# CC_amplifier.net
KiCad netlist of a schematic drawn in Altium Designer
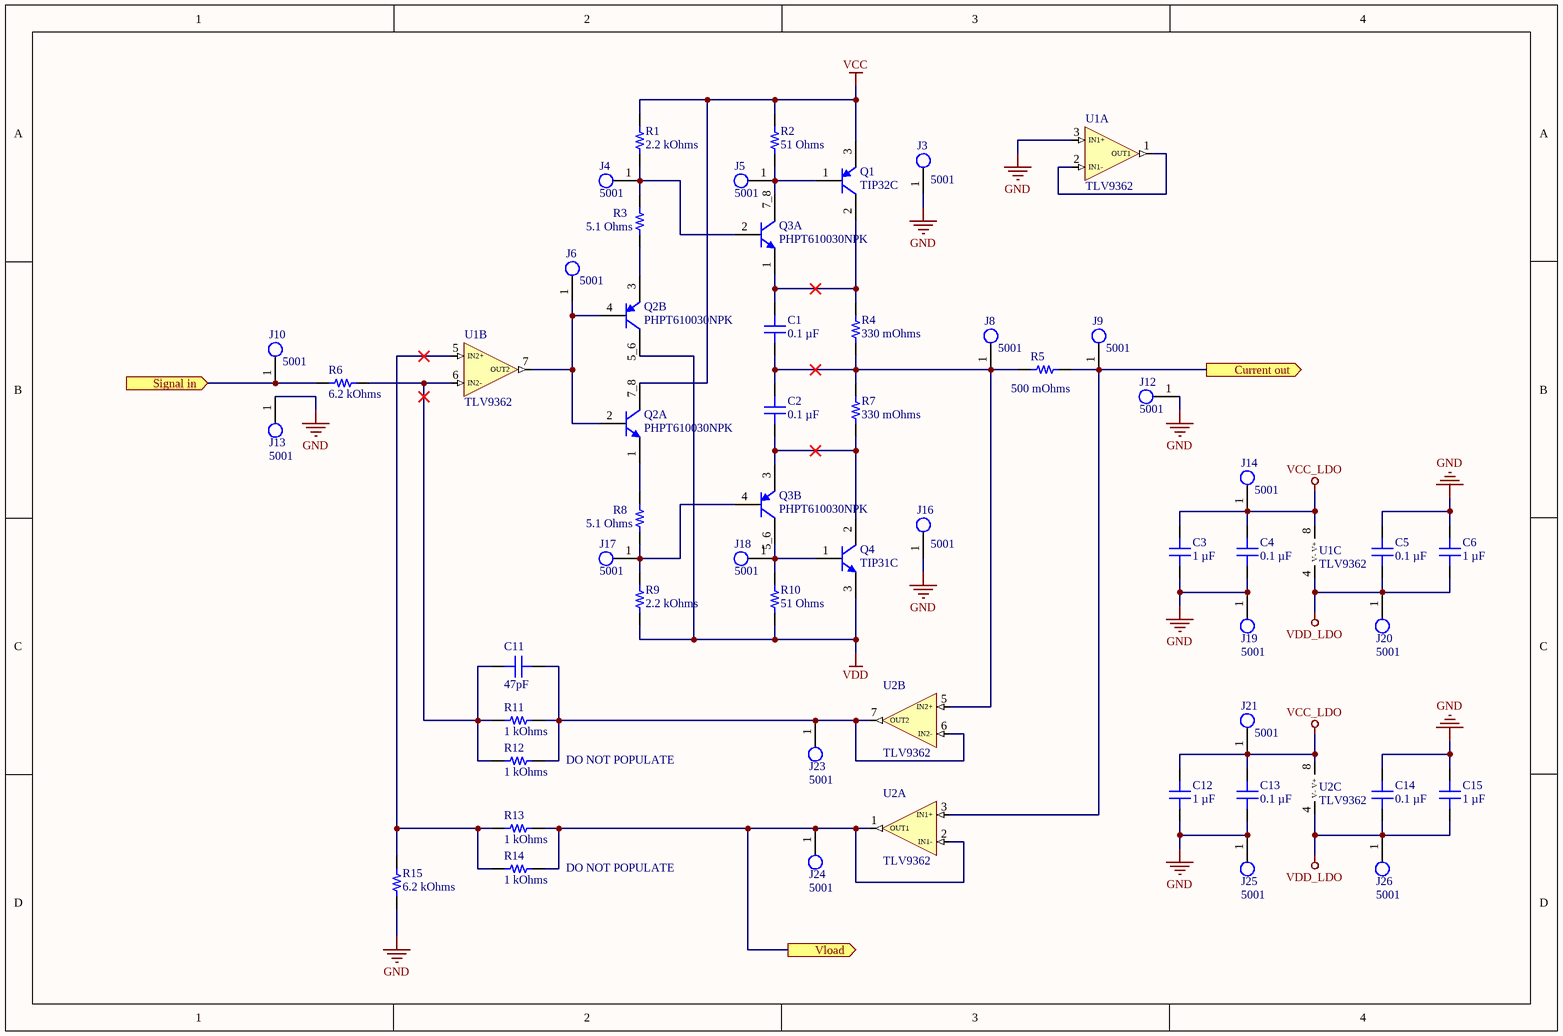
[diagram p0: CC_amplifier.SchDoc]

(export (version "E")
  (design (tool "Eeschema 10.0.6"))
  (components
    (comp (ref "C1")
      (value "0.1 µF")
      (footprint "CAP 1206_3216 - 0.8MM")
      (description "CAP CER 0.1UF 50V X7R 1206")
      (fields
        (field (name "PART NUMBER") "885012208087")
        (field (name "CAPACITANCE") "0.1 µF")
        (field (name "MANUFACTURER") "Würth Elektronik")
      )
      (libsource (lib "Celestial Altium Library - altium_library") (part "Capacitor"))
    )
    (comp (ref "C2")
      (value "0.1 µF")
      (footprint "CAP 1206_3216 - 0.8MM")
      (description "CAP CER 0.1UF 50V X7R 1206")
      (fields
        (field (name "PART NUMBER") "885012208087")
        (field (name "CAPACITANCE") "0.1 µF")
        (field (name "MANUFACTURER") "Würth Elektronik")
      )
      (libsource (lib "Celestial Altium Library - altium_library") (part "Capacitor"))
    )
    (comp (ref "C3")
      (value "1 µF")
      (footprint "CAP 1206_3216 - 0.8MM")
      (description "CAP CER 1UF 50V X7R 1206")
      (fields
        (field (name "PART NUMBER") "885012208093")
        (field (name "CAPACITANCE") "1 µF")
        (field (name "MANUFACTURER") "Würth Elektronik")
      )
      (libsource (lib "Celestial Altium Library - altium_library") (part "Capacitor"))
    )
    (comp (ref "C4")
      (value "0.1 µF")
      (footprint "CAP 1206_3216 - 0.8MM")
      (description "CAP CER 0.1UF 50V X7R 1206")
      (fields
        (field (name "PART NUMBER") "885012208087")
        (field (name "CAPACITANCE") "0.1 µF")
        (field (name "MANUFACTURER") "Würth Elektronik")
      )
      (libsource (lib "Celestial Altium Library - altium_library") (part "Capacitor"))
    )
    (comp (ref "C5")
      (value "0.1 µF")
      (footprint "CAP 1206_3216 - 0.8MM")
      (description "CAP CER 0.1UF 50V X7R 1206")
      (fields
        (field (name "PART NUMBER") "885012208087")
        (field (name "CAPACITANCE") "0.1 µF")
        (field (name "MANUFACTURER") "Würth Elektronik")
      )
      (libsource (lib "Celestial Altium Library - altium_library") (part "Capacitor"))
    )
    (comp (ref "C6")
      (value "1 µF")
      (footprint "CAP 1206_3216 - 0.8MM")
      (description "CAP CER 1UF 50V X7R 1206")
      (fields
        (field (name "PART NUMBER") "885012208093")
        (field (name "CAPACITANCE") "1 µF")
        (field (name "MANUFACTURER") "Würth Elektronik")
      )
      (libsource (lib "Celestial Altium Library - altium_library") (part "Capacitor"))
    )
    (comp (ref "C11")
      (value "47pF")
      (footprint "CAP 1206_3216 - 1.8MM")
      (description "CAP CER 47PF 1KV C0G/NP0 1206")
      (fields
        (field (name "PART NUMBER") "1206AA470KAT1A")
        (field (name "CAPACITANCE") "47pF")
        (field (name "MANUFACTURER") "AVX Corporation")
      )
      (libsource (lib "Celestial Altium Library - altium_library") (part "Capacitor"))
    )
    (comp (ref "C12")
      (value "1 µF")
      (footprint "CAP 1206_3216 - 0.8MM")
      (description "CAP CER 1UF 50V X7R 1206")
      (fields
        (field (name "PART NUMBER") "885012208093")
        (field (name "CAPACITANCE") "1 µF")
        (field (name "MANUFACTURER") "Würth Elektronik")
      )
      (libsource (lib "Celestial Altium Library - altium_library") (part "Capacitor"))
    )
    (comp (ref "C13")
      (value "0.1 µF")
      (footprint "CAP 1206_3216 - 0.8MM")
      (description "CAP CER 0.1UF 50V X7R 1206")
      (fields
        (field (name "PART NUMBER") "885012208087")
        (field (name "CAPACITANCE") "0.1 µF")
        (field (name "MANUFACTURER") "Würth Elektronik")
      )
      (libsource (lib "Celestial Altium Library - altium_library") (part "Capacitor"))
    )
    (comp (ref "C14")
      (value "0.1 µF")
      (footprint "CAP 1206_3216 - 0.8MM")
      (description "CAP CER 0.1UF 50V X7R 1206")
      (fields
        (field (name "PART NUMBER") "885012208087")
        (field (name "CAPACITANCE") "0.1 µF")
        (field (name "MANUFACTURER") "Würth Elektronik")
      )
      (libsource (lib "Celestial Altium Library - altium_library") (part "Capacitor"))
    )
    (comp (ref "C15")
      (value "1 µF")
      (footprint "CAP 1206_3216 - 0.8MM")
      (description "CAP CER 1UF 50V X7R 1206")
      (fields
        (field (name "PART NUMBER") "885012208093")
        (field (name "CAPACITANCE") "1 µF")
        (field (name "MANUFACTURER") "Würth Elektronik")
      )
      (libsource (lib "Celestial Altium Library - altium_library") (part "Capacitor"))
    )
    (comp (ref "J3")
      (value "5001")
      (footprint "FP-5001-MFG")
      (description "PC TEST POINT MINIATURE BLACK")
      (libsource (lib "za_koncar") (part "CMP-2000-05181-2"))
    )
    (comp (ref "J4")
      (value "5001")
      (footprint "FP-5001-MFG")
      (description "PC TEST POINT MINIATURE BLACK")
      (libsource (lib "za_koncar") (part "CMP-2000-05181-2"))
    )
    (comp (ref "J5")
      (value "5001")
      (footprint "FP-5001-MFG")
      (description "PC TEST POINT MINIATURE BLACK")
      (libsource (lib "za_koncar") (part "CMP-2000-05181-2"))
    )
    (comp (ref "J6")
      (value "5001")
      (footprint "FP-5001-MFG")
      (description "PC TEST POINT MINIATURE BLACK")
      (libsource (lib "za_koncar") (part "CMP-2000-05181-2"))
    )
    (comp (ref "J8")
      (value "5001")
      (footprint "FP-5001-MFG")
      (description "PC TEST POINT MINIATURE BLACK")
      (libsource (lib "za_koncar") (part "CMP-2000-05181-2"))
    )
    (comp (ref "J9")
      (value "5001")
      (footprint "FP-5001-MFG")
      (description "PC TEST POINT MINIATURE BLACK")
      (libsource (lib "za_koncar") (part "CMP-2000-05181-2"))
    )
    (comp (ref "J10")
      (value "5001")
      (footprint "FP-5001-MFG")
      (description "PC TEST POINT MINIATURE BLACK")
      (libsource (lib "za_koncar") (part "CMP-2000-05181-2"))
    )
    (comp (ref "J12")
      (value "5001")
      (footprint "FP-5001-MFG")
      (description "PC TEST POINT MINIATURE BLACK")
      (libsource (lib "za_koncar") (part "CMP-2000-05181-2"))
    )
    (comp (ref "J13")
      (value "5001")
      (footprint "FP-5001-MFG")
      (description "PC TEST POINT MINIATURE BLACK")
      (libsource (lib "za_koncar") (part "CMP-2000-05181-2"))
    )
    (comp (ref "J14")
      (value "5001")
      (footprint "FP-5001-MFG")
      (description "PC TEST POINT MINIATURE BLACK")
      (libsource (lib "za_koncar") (part "CMP-2000-05181-2"))
    )
    (comp (ref "J16")
      (value "5001")
      (footprint "FP-5001-MFG")
      (description "PC TEST POINT MINIATURE BLACK")
      (libsource (lib "za_koncar") (part "CMP-2000-05181-2"))
    )
    (comp (ref "J17")
      (value "5001")
      (footprint "FP-5001-MFG")
      (description "PC TEST POINT MINIATURE BLACK")
      (libsource (lib "za_koncar") (part "CMP-2000-05181-2"))
    )
    (comp (ref "J18")
      (value "5001")
      (footprint "FP-5001-MFG")
      (description "PC TEST POINT MINIATURE BLACK")
      (libsource (lib "za_koncar") (part "CMP-2000-05181-2"))
    )
    (comp (ref "J19")
      (value "5001")
      (footprint "FP-5001-MFG")
      (description "PC TEST POINT MINIATURE BLACK")
      (libsource (lib "za_koncar") (part "CMP-2000-05181-2"))
    )
    (comp (ref "J20")
      (value "5001")
      (footprint "FP-5001-MFG")
      (description "PC TEST POINT MINIATURE BLACK")
      (libsource (lib "za_koncar") (part "CMP-2000-05181-2"))
    )
    (comp (ref "J21")
      (value "5001")
      (footprint "FP-5001-MFG")
      (description "PC TEST POINT MINIATURE BLACK")
      (libsource (lib "za_koncar") (part "CMP-2000-05181-2"))
    )
    (comp (ref "J23")
      (value "5001")
      (footprint "FP-5001-MFG")
      (description "PC TEST POINT MINIATURE BLACK")
      (libsource (lib "za_koncar") (part "CMP-2000-05181-2"))
    )
    (comp (ref "J24")
      (value "5001")
      (footprint "FP-5001-MFG")
      (description "PC TEST POINT MINIATURE BLACK")
      (libsource (lib "za_koncar") (part "CMP-2000-05181-2"))
    )
    (comp (ref "J25")
      (value "5001")
      (footprint "FP-5001-MFG")
      (description "PC TEST POINT MINIATURE BLACK")
      (libsource (lib "za_koncar") (part "CMP-2000-05181-2"))
    )
    (comp (ref "J26")
      (value "5001")
      (footprint "FP-5001-MFG")
      (description "PC TEST POINT MINIATURE BLACK")
      (libsource (lib "za_koncar") (part "CMP-2000-05181-2"))
    )
    (comp (ref "Q1")
      (value "TIP32C")
      (footprint "ONSC-TO-220-3-221A-09")
      (description "Complementary Silicon Plastic Power Transistor, 3-Pin TO-220, Tube")
      (fields (field (name "MANUFACTURER") "On Semiconductor"))
      (libsource (lib "ON Semi General Purpose Transistors") (part "TIP32C"))
    )
    (comp (ref "Q2")
      (value "PHPT610030NPK")
      (footprint "TRANS_BUK9K18-40E,115")
      (libsource (lib "za_koncar") (part "PHPT610030NPK"))
    )
    (comp (ref "Q3")
      (value "PHPT610030NPK")
      (footprint "TRANS_BUK9K18-40E,115")
      (libsource (lib "za_koncar") (part "PHPT610030NPK"))
    )
    (comp (ref "Q4")
      (value "TIP31C")
      (footprint "ONSC-TO-220-3-221A-09")
      (description "Complementary Silicon Plastic Power Transistor, 3-Pin TO-220, Tube")
      (fields (field (name "MANUFACTURER") "On Semiconductor"))
      (libsource (lib "ON Semi General Purpose Transistors") (part "TIP31C"))
    )
    (comp (ref "R1")
      (value "2.2 kOhms")
      (footprint "RES 1206_3216")
      (description "RES SMD 2.2K OHM 5% 1/4W 1206")
      (fields
        (field (name "PART NUMBER") "ERJ-8GEYJ222V")
        (field (name "MANUFACTURER") "Panasonic Electronic Components")
      )
      (libsource (lib "Celestial Altium Library - altium_library") (part "Resistor"))
    )
    (comp (ref "R2")
      (value "51 Ohms")
      (footprint "RES 1206_3216")
      (description "RES SMD 51 OHM 5% 1/4W 1206")
      (fields
        (field (name "PART NUMBER") "ERJ-8GEYJ510V")
        (field (name "MANUFACTURER") "Panasonic Electronic Components")
      )
      (libsource (lib "Celestial Altium Library - altium_library") (part "Resistor"))
    )
    (comp (ref "R3")
      (value "5.1 Ohms")
      (footprint "RES 1206_3216")
      (description "RES SMD 5.1 OHM 5% 1/4W 1206")
      (fields
        (field (name "PART NUMBER") "ERJ-8GEYJ5R1V")
        (field (name "MANUFACTURER") "Panasonic Electronic Components")
      )
      (libsource (lib "Celestial Altium Library - altium_library") (part "Resistor"))
    )
    (comp (ref "R4")
      (value "330 mOhms")
      (footprint "STACKPOLE CSR2512")
      (description "RES 0.33 OHM 1% 2W 2512")
      (fields
        (field (name "PART NUMBER") "CSRN2512FKR330")
        (field (name "MANUFACTURER") "Stackpole Electronics Inc")
      )
      (libsource (lib "Celestial Altium Library - altium_library") (part "Resistor"))
    )
    (comp (ref "R5")
      (value "500 mOhms")
      (footprint "STACKPOLE CSR2512")
      (description "RES 0.5 OHM 1% 2W 2512")
      (fields
        (field (name "PART NUMBER") "CSRN2512FKR500")
        (field (name "MANUFACTURER") "Stackpole Electronics Inc")
      )
      (libsource (lib "Celestial Altium Library - altium_library") (part "Resistor"))
    )
    (comp (ref "R6")
      (value "6.2 kOhms")
      (footprint "RES 1206_3216")
      (description "RES SMD 6.2K OHM 0.1% 1/4W 1206")
      (fields
        (field (name "PART NUMBER") "ERA-8AEB622V")
        (field (name "MANUFACTURER") "Panasonic Electronic Components")
      )
      (libsource (lib "Celestial Altium Library - altium_library") (part "Resistor"))
    )
    (comp (ref "R7")
      (value "330 mOhms")
      (footprint "STACKPOLE CSR2512")
      (description "RES 0.33 OHM 1% 2W 2512")
      (fields
        (field (name "PART NUMBER") "CSRN2512FKR330")
        (field (name "MANUFACTURER") "Stackpole Electronics Inc")
      )
      (libsource (lib "Celestial Altium Library - altium_library") (part "Resistor"))
    )
    (comp (ref "R8")
      (value "5.1 Ohms")
      (footprint "RES 1206_3216")
      (description "RES SMD 5.1 OHM 5% 1/4W 1206")
      (fields
        (field (name "PART NUMBER") "ERJ-8GEYJ5R1V")
        (field (name "MANUFACTURER") "Panasonic Electronic Components")
      )
      (libsource (lib "Celestial Altium Library - altium_library") (part "Resistor"))
    )
    (comp (ref "R9")
      (value "2.2 kOhms")
      (footprint "RES 1206_3216")
      (description "RES SMD 2.2K OHM 5% 1/4W 1206")
      (fields
        (field (name "PART NUMBER") "ERJ-8GEYJ222V")
        (field (name "MANUFACTURER") "Panasonic Electronic Components")
      )
      (libsource (lib "Celestial Altium Library - altium_library") (part "Resistor"))
    )
    (comp (ref "R10")
      (value "51 Ohms")
      (footprint "RES 1206_3216")
      (description "RES SMD 51 OHM 5% 1/4W 1206")
      (fields
        (field (name "PART NUMBER") "ERJ-8GEYJ510V")
        (field (name "MANUFACTURER") "Panasonic Electronic Components")
      )
      (libsource (lib "Celestial Altium Library - altium_library") (part "Resistor"))
    )
    (comp (ref "R11")
      (value "1 kOhms")
      (footprint "RES 1206_3216")
      (description "RES SMD 1K OHM 0.1% 1/4W 1206")
      (fields
        (field (name "PART NUMBER") "ERA-8AEB102V")
        (field (name "MANUFACTURER") "Panasonic Electronic Components")
      )
      (libsource (lib "Celestial Altium Library - altium_library") (part "Resistor"))
    )
    (comp (ref "R12")
      (value "1 kOhms")
      (footprint "RES 1206_3216")
      (description "RES SMD 1K OHM 0.1% 1/4W 1206")
      (fields
        (field (name "PART NUMBER") "ERA-8AEB102V")
        (field (name "MANUFACTURER") "Panasonic Electronic Components")
      )
      (libsource (lib "Celestial Altium Library - altium_library") (part "Resistor"))
    )
    (comp (ref "R13")
      (value "1 kOhms")
      (footprint "RES 1206_3216")
      (description "RES SMD 1K OHM 0.1% 1/4W 1206")
      (fields
        (field (name "PART NUMBER") "ERA-8AEB102V")
        (field (name "MANUFACTURER") "Panasonic Electronic Components")
      )
      (libsource (lib "Celestial Altium Library - altium_library") (part "Resistor"))
    )
    (comp (ref "R14")
      (value "1 kOhms")
      (footprint "RES 1206_3216")
      (description "RES SMD 1K OHM 0.1% 1/4W 1206")
      (fields
        (field (name "PART NUMBER") "ERA-8AEB102V")
        (field (name "MANUFACTURER") "Panasonic Electronic Components")
      )
      (libsource (lib "Celestial Altium Library - altium_library") (part "Resistor"))
    )
    (comp (ref "R15")
      (value "6.2 kOhms")
      (footprint "RES 1206_3216")
      (description "RES SMD 6.2K OHM 0.1% 1/4W 1206")
      (fields
        (field (name "PART NUMBER") "ERA-8AEB622V")
        (field (name "MANUFACTURER") "Panasonic Electronic Components")
      )
      (libsource (lib "Celestial Altium Library - altium_library") (part "Resistor"))
    )
    (comp (ref "U1")
      (value "TLV9362")
      (footprint "za_koncar:SOIC8-127P600X175-8N")
      (description "TLV936x 10-MHz, 40-V, RRO, Operational Amplifie")
      (libsource (lib "za_koncar") (part "TLV9362"))
    )
    (comp (ref "U2")
      (value "TLV9362")
      (footprint "za_koncar:SOIC8-127P600X175-8N")
      (description "TLV936x 10-MHz, 40-V, RRO, Operational Amplifie")
      (libsource (lib "za_koncar") (part "TLV9362"))
    )
  )
  (nets
    (net (code "1") (name "/Current out") (class "Default")
      (node (ref "J9") (pin "1") (pinfunction "1_1") (pintype "passive"))
      (node (ref "R5") (pin "1") (pinfunction "1_1") (pintype "passive"))
      (node (ref "U2") (pin "3") (pinfunction "IN1+_3") (pintype "input"))
    )
    (net (code "2") (name "/Signal in") (class "Default")
      (node (ref "J10") (pin "1") (pinfunction "1_1") (pintype "passive"))
      (node (ref "R6") (pin "2") (pinfunction "2_2") (pintype "passive"))
    )
    (net (code "3") (name "/Vload") (class "Default")
      (node (ref "J24") (pin "1") (pinfunction "1_1") (pintype "passive"))
      (node (ref "R13") (pin "2") (pinfunction "2_2") (pintype "passive"))
      (node (ref "R14") (pin "2") (pinfunction "2_2") (pintype "passive"))
      (node (ref "U2") (pin "1") (pinfunction "OUT1_1") (pintype "output"))
      (node (ref "U2") (pin "2") (pinfunction "IN1-_2") (pintype "input"))
    )
    (net (code "4") (name "GND") (class "Default")
      (node (ref "C12") (pin "1") (pinfunction "1_1") (pintype "passive"))
      (node (ref "C13") (pin "1") (pinfunction "1_1") (pintype "passive"))
      (node (ref "C14") (pin "2") (pinfunction "2_2") (pintype "passive"))
      (node (ref "C15") (pin "2") (pinfunction "2_2") (pintype "passive"))
      (node (ref "C3") (pin "1") (pinfunction "1_1") (pintype "passive"))
      (node (ref "C4") (pin "1") (pinfunction "1_1") (pintype "passive"))
      (node (ref "C5") (pin "2") (pinfunction "2_2") (pintype "passive"))
      (node (ref "C6") (pin "2") (pinfunction "2_2") (pintype "passive"))
      (node (ref "J12") (pin "1") (pinfunction "1_1") (pintype "passive"))
      (node (ref "J13") (pin "1") (pinfunction "1_1") (pintype "passive"))
      (node (ref "J16") (pin "1") (pinfunction "1_1") (pintype "passive"))
      (node (ref "J19") (pin "1") (pinfunction "1_1") (pintype "passive"))
      (node (ref "J25") (pin "1") (pinfunction "1_1") (pintype "passive"))
      (node (ref "J3") (pin "1") (pinfunction "1_1") (pintype "passive"))
      (node (ref "R15") (pin "1") (pinfunction "1_1") (pintype "passive"))
      (node (ref "U1") (pin "3") (pinfunction "IN1+_3") (pintype "input"))
    )
    (net (code "5") (name "Net-(Q1-B)") (class "Default")
      (node (ref "J5") (pin "1") (pinfunction "1_1") (pintype "passive"))
      (node (ref "Q1") (pin "1") (pinfunction "B_1") (pintype "passive"))
      (node (ref "Q3") (pin "7_8") (pinfunction "C1_7_8") (pintype "passive"))
      (node (ref "R2") (pin "1") (pinfunction "1_1") (pintype "passive"))
    )
    (net (code "6") (name "Net-(Q1-C)") (class "Default")
      (node (ref "C1") (pin "2") (pinfunction "2_2") (pintype "passive"))
      (node (ref "Q1") (pin "2") (pinfunction "C_2") (pintype "passive"))
      (node (ref "Q3") (pin "1") (pinfunction "E1_1") (pintype "passive"))
      (node (ref "R4") (pin "2") (pinfunction "2_2") (pintype "passive"))
    )
    (net (code "7") (name "Net-(Q2A-B1)") (class "Default")
      (node (ref "J6") (pin "1") (pinfunction "1_1") (pintype "passive"))
      (node (ref "Q2") (pin "2") (pinfunction "B1_2") (pintype "passive"))
      (node (ref "Q2") (pin "4") (pinfunction "B2_4") (pintype "passive"))
      (node (ref "U1") (pin "7") (pinfunction "OUT2_7") (pintype "output"))
    )
    (net (code "8") (name "Net-(Q2A-E1)") (class "Default")
      (node (ref "Q2") (pin "1") (pinfunction "E1_1") (pintype "passive"))
      (node (ref "R8") (pin "2") (pinfunction "2_2") (pintype "passive"))
    )
    (net (code "9") (name "Net-(Q2B-E2)") (class "Default")
      (node (ref "Q2") (pin "3") (pinfunction "E2_3") (pintype "passive"))
      (node (ref "R3") (pin "1") (pinfunction "1_1") (pintype "passive"))
    )
    (net (code "10") (name "Net-(Q3A-B1)") (class "Default")
      (node (ref "J4") (pin "1") (pinfunction "1_1") (pintype "passive"))
      (node (ref "Q3") (pin "2") (pinfunction "B1_2") (pintype "passive"))
      (node (ref "R1") (pin "1") (pinfunction "1_1") (pintype "passive"))
      (node (ref "R3") (pin "2") (pinfunction "2_2") (pintype "passive"))
    )
    (net (code "11") (name "Net-(Q3B-B2)") (class "Default")
      (node (ref "J17") (pin "1") (pinfunction "1_1") (pintype "passive"))
      (node (ref "Q3") (pin "4") (pinfunction "B2_4") (pintype "passive"))
      (node (ref "R8") (pin "1") (pinfunction "1_1") (pintype "passive"))
      (node (ref "R9") (pin "2") (pinfunction "2_2") (pintype "passive"))
    )
    (net (code "12") (name "Net-(Q3B-C2)") (class "Default")
      (node (ref "J18") (pin "1") (pinfunction "1_1") (pintype "passive"))
      (node (ref "Q3") (pin "5_6") (pinfunction "C2_5_6") (pintype "passive"))
      (node (ref "Q4") (pin "1") (pinfunction "B_1") (pintype "passive"))
      (node (ref "R10") (pin "2") (pinfunction "2_2") (pintype "passive"))
    )
    (net (code "13") (name "Net-(Q3B-E2)") (class "Default")
      (node (ref "C2") (pin "1") (pinfunction "1_1") (pintype "passive"))
      (node (ref "Q3") (pin "3") (pinfunction "E2_3") (pintype "passive"))
      (node (ref "Q4") (pin "2") (pinfunction "C_2") (pintype "passive"))
      (node (ref "R7") (pin "1") (pinfunction "1_1") (pintype "passive"))
    )
    (net (code "14") (name "Net-(U1A-IN1-)") (class "Default")
      (node (ref "U1") (pin "1") (pinfunction "OUT1_1") (pintype "output"))
      (node (ref "U1") (pin "2") (pinfunction "IN1-_2") (pintype "input"))
    )
    (net (code "15") (name "Net-(U1B-IN2+)") (class "Default")
      (node (ref "R13") (pin "1") (pinfunction "1_1") (pintype "passive"))
      (node (ref "R14") (pin "1") (pinfunction "1_1") (pintype "passive"))
      (node (ref "R15") (pin "2") (pinfunction "2_2") (pintype "passive"))
      (node (ref "U1") (pin "5") (pinfunction "IN2+_5") (pintype "input"))
    )
    (net (code "16") (name "Net-(U1B-IN2-)") (class "Default")
      (node (ref "C11") (pin "1") (pinfunction "1_1") (pintype "passive"))
      (node (ref "R11") (pin "1") (pinfunction "1_1") (pintype "passive"))
      (node (ref "R12") (pin "1") (pinfunction "1_1") (pintype "passive"))
      (node (ref "R6") (pin "1") (pinfunction "1_1") (pintype "passive"))
      (node (ref "U1") (pin "6") (pinfunction "IN2-_6") (pintype "input"))
    )
    (net (code "17") (name "Net-(U2B-IN2+)") (class "Default")
      (node (ref "C1") (pin "1") (pinfunction "1_1") (pintype "passive"))
      (node (ref "C2") (pin "2") (pinfunction "2_2") (pintype "passive"))
      (node (ref "J8") (pin "1") (pinfunction "1_1") (pintype "passive"))
      (node (ref "R4") (pin "1") (pinfunction "1_1") (pintype "passive"))
      (node (ref "R5") (pin "2") (pinfunction "2_2") (pintype "passive"))
      (node (ref "R7") (pin "2") (pinfunction "2_2") (pintype "passive"))
      (node (ref "U2") (pin "5") (pinfunction "IN2+_5") (pintype "input"))
    )
    (net (code "18") (name "Net-(U2B-IN2-)") (class "Default")
      (node (ref "C11") (pin "2") (pinfunction "2_2") (pintype "passive"))
      (node (ref "J23") (pin "1") (pinfunction "1_1") (pintype "passive"))
      (node (ref "R11") (pin "2") (pinfunction "2_2") (pintype "passive"))
      (node (ref "R12") (pin "2") (pinfunction "2_2") (pintype "passive"))
      (node (ref "U2") (pin "6") (pinfunction "IN2-_6") (pintype "input"))
      (node (ref "U2") (pin "7") (pinfunction "OUT2_7") (pintype "output"))
    )
    (net (code "19") (name "VCC") (class "Default")
      (node (ref "Q1") (pin "3") (pinfunction "E_3") (pintype "passive"))
      (node (ref "Q2") (pin "7_8") (pinfunction "C1_7_8") (pintype "passive"))
      (node (ref "R1") (pin "2") (pinfunction "2_2") (pintype "passive"))
      (node (ref "R2") (pin "2") (pinfunction "2_2") (pintype "passive"))
    )
    (net (code "20") (name "VCC_LDO") (class "Default")
      (node (ref "C12") (pin "2") (pinfunction "2_2") (pintype "passive"))
      (node (ref "C13") (pin "2") (pinfunction "2_2") (pintype "passive"))
      (node (ref "C3") (pin "2") (pinfunction "2_2") (pintype "passive"))
      (node (ref "C4") (pin "2") (pinfunction "2_2") (pintype "passive"))
      (node (ref "J14") (pin "1") (pinfunction "1_1") (pintype "passive"))
      (node (ref "J21") (pin "1") (pinfunction "1_1") (pintype "passive"))
      (node (ref "U1") (pin "8") (pinfunction "V+_8") (pintype "power_in"))
      (node (ref "U2") (pin "8") (pinfunction "V+_8") (pintype "power_in"))
    )
    (net (code "21") (name "VDD") (class "Default")
      (node (ref "Q2") (pin "5_6") (pinfunction "C2_5_6") (pintype "passive"))
      (node (ref "Q4") (pin "3") (pinfunction "E_3") (pintype "passive"))
      (node (ref "R10") (pin "1") (pinfunction "1_1") (pintype "passive"))
      (node (ref "R9") (pin "1") (pinfunction "1_1") (pintype "passive"))
    )
    (net (code "22") (name "VDD_LDO") (class "Default")
      (node (ref "C14") (pin "1") (pinfunction "1_1") (pintype "passive"))
      (node (ref "C15") (pin "1") (pinfunction "1_1") (pintype "passive"))
      (node (ref "C5") (pin "1") (pinfunction "1_1") (pintype "passive"))
      (node (ref "C6") (pin "1") (pinfunction "1_1") (pintype "passive"))
      (node (ref "J20") (pin "1") (pinfunction "1_1") (pintype "passive"))
      (node (ref "J26") (pin "1") (pinfunction "1_1") (pintype "passive"))
      (node (ref "U1") (pin "4") (pinfunction "V-_4") (pintype "power_in"))
      (node (ref "U2") (pin "4") (pinfunction "V-_4") (pintype "power_in"))
    )
  )
)
